# schema0_1.net
KiCad netlist of a schematic drawn in EAGLE
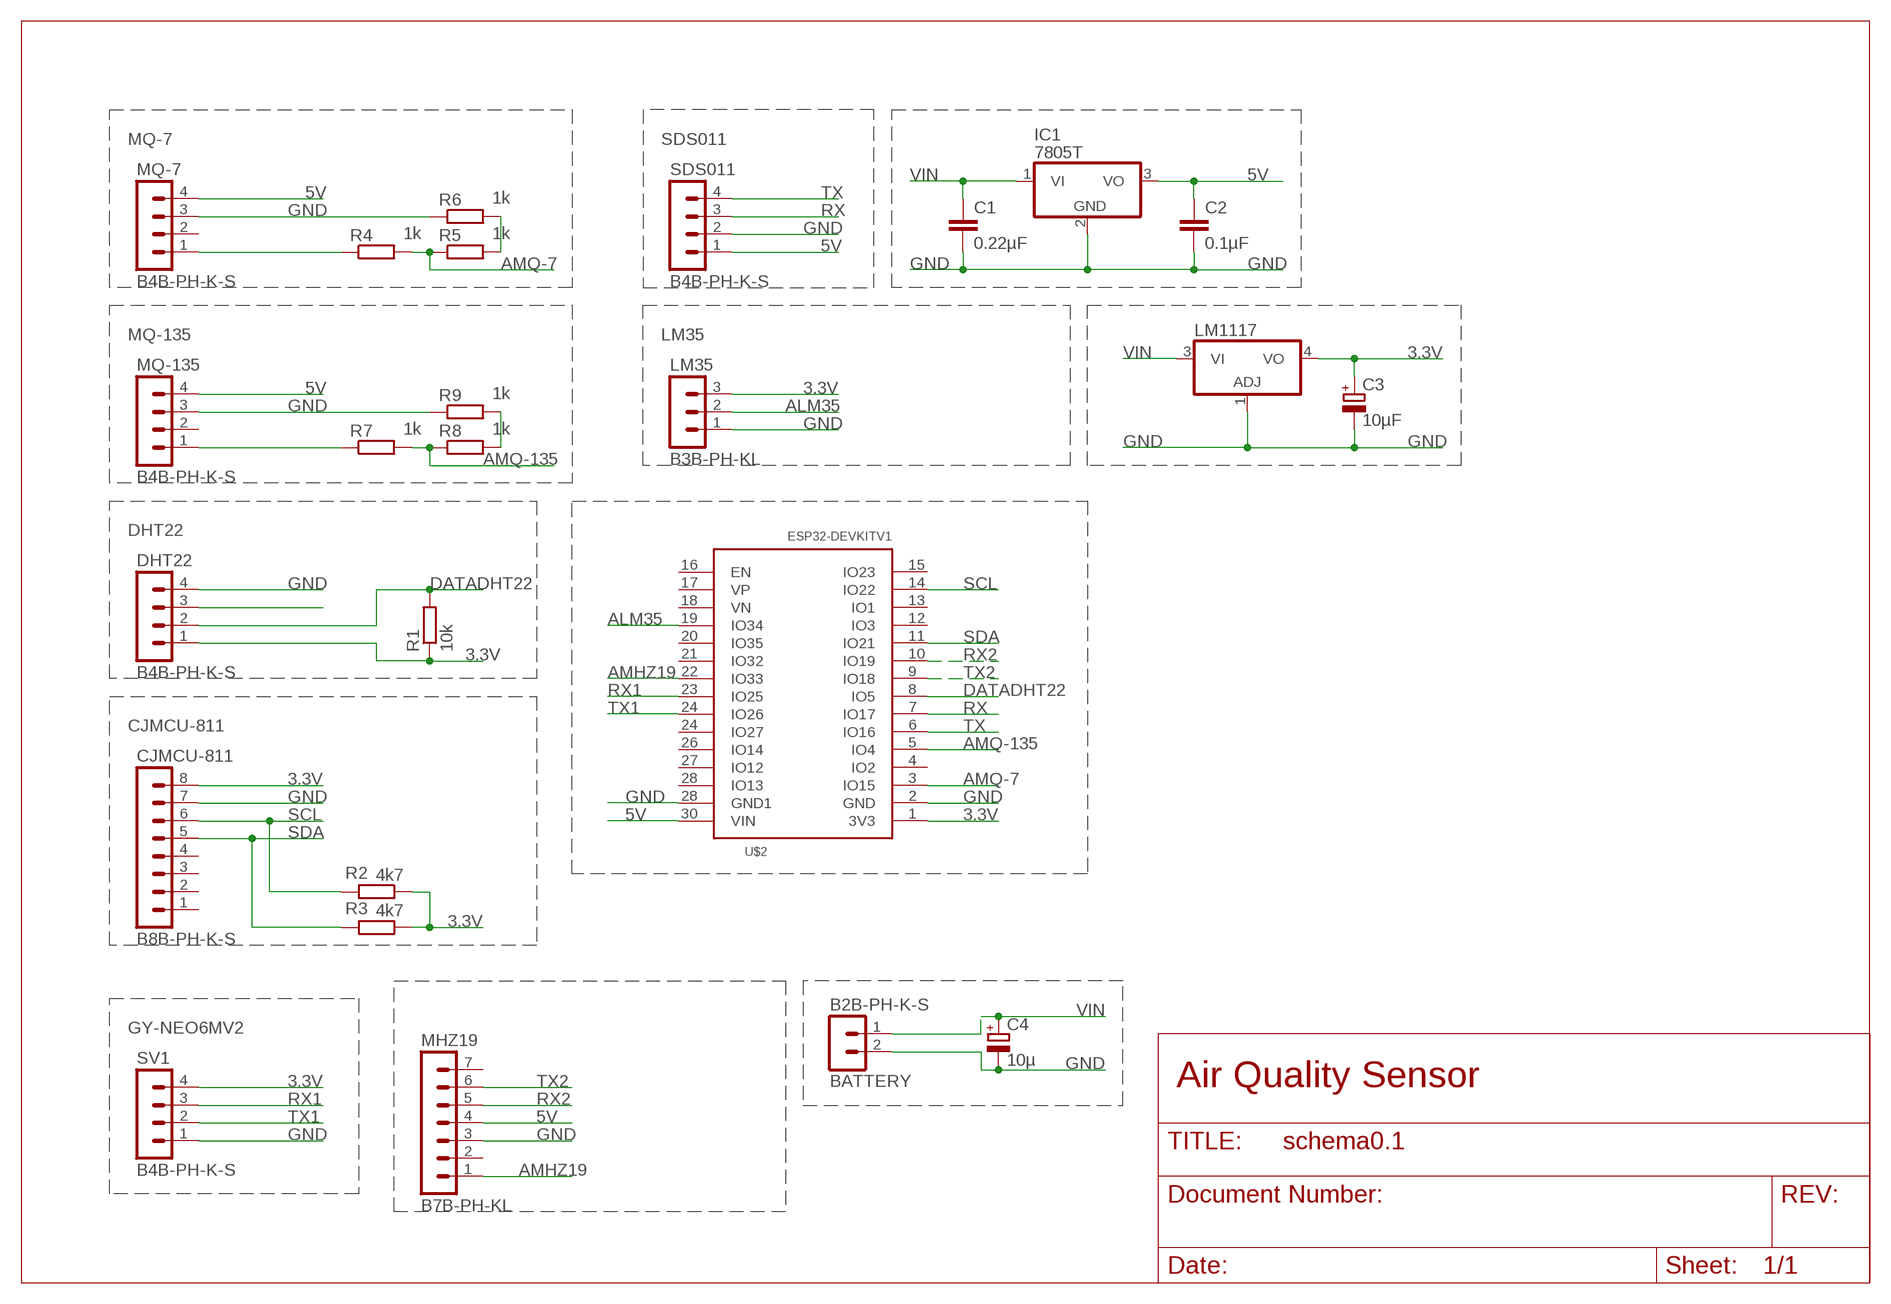
[diagram p0: schematic, sheet 1]

(export (version "E")
  (design (tool "Eeschema 10.0.6"))
  (components
    (comp (ref "BATTERY")
      (value "B2B-PH-K-S")
      (footprint "eagle-import:B2B-PH-K-S")
      (libsource (lib "eagle-import") (part "B2B-PH-K-S"))
    )
    (comp (ref "C1")
      (value "0.22µF")
      (footprint "eagle-import:C0805")
      (libsource (lib "eagle-import") (part "C-EUC0805"))
    )
    (comp (ref "C2")
      (value "0.1µF")
      (footprint "eagle-import:C0805")
      (libsource (lib "eagle-import") (part "C-EUC0805"))
    )
    (comp (ref "C3")
      (value "10µF")
      (footprint "eagle-import:E2-5")
      (libsource (lib "eagle-import") (part "CPOL-EUE2-5"))
    )
    (comp (ref "C4")
      (value "10µ")
      (footprint "eagle-import:E2-5")
      (libsource (lib "eagle-import") (part "CPOL-EUE2-5"))
    )
    (comp (ref "CJMCU-811")
      (value "B8B-PH-K-S")
      (footprint "eagle-import:B8B-PH-K-S")
      (libsource (lib "eagle-import") (part "B8B-PH-K-S"))
    )
    (comp (ref "DHT22")
      (value "B4B-PH-K-S")
      (footprint "eagle-import:B4B-PH-K-S")
      (libsource (lib "eagle-import") (part "B4B-PH-K-S"))
    )
    (comp (ref "IC1")
      (value "7805T")
      (footprint "eagle-import:TO220H")
      (libsource (lib "eagle-import") (part "78T05"))
    )
    (comp (ref "LM35")
      (value "B3B-PH-KL")
      (footprint "eagle-import:B3B-PH-K-S")
      (libsource (lib "eagle-import") (part "B3B-PH-KL"))
    )
    (comp (ref "LM1117")
      (value "317EMP")
      (footprint "eagle-import:SOT223")
      (libsource (lib "eagle-import") (part "317EMP"))
    )
    (comp (ref "MHZ19")
      (value "B7B-PH-KL")
      (footprint "eagle-import:B7B-PH-K-S")
      (libsource (lib "eagle-import") (part "B7B-PH-KL"))
    )
    (comp (ref "MQ-7")
      (value "B4B-PH-K-S")
      (footprint "eagle-import:B4B-PH-K-S")
      (libsource (lib "eagle-import") (part "B4B-PH-K-S"))
    )
    (comp (ref "MQ-135")
      (value "B4B-PH-K-S")
      (footprint "eagle-import:B4B-PH-K-S")
      (libsource (lib "eagle-import") (part "B4B-PH-K-S"))
    )
    (comp (ref "R1")
      (value "10k")
      (footprint "eagle-import:R0805")
      (libsource (lib "eagle-import") (part "R-EU_R0805"))
    )
    (comp (ref "R2")
      (value "4k7")
      (footprint "eagle-import:R0805")
      (libsource (lib "eagle-import") (part "R-EU_R0805"))
    )
    (comp (ref "R3")
      (value "4k7")
      (footprint "eagle-import:R0805")
      (libsource (lib "eagle-import") (part "R-EU_R0805"))
    )
    (comp (ref "R4")
      (value "1k")
      (footprint "eagle-import:0207_10")
      (libsource (lib "eagle-import") (part "R-EU_0207/10"))
    )
    (comp (ref "R5")
      (value "1k")
      (footprint "eagle-import:R0805")
      (libsource (lib "eagle-import") (part "R-EU_R0805"))
    )
    (comp (ref "R6")
      (value "1k")
      (footprint "eagle-import:R0805")
      (libsource (lib "eagle-import") (part "R-EU_R0805"))
    )
    (comp (ref "R7")
      (value "1k")
      (footprint "eagle-import:R0805")
      (libsource (lib "eagle-import") (part "R-EU_R0805"))
    )
    (comp (ref "R8")
      (value "1k")
      (footprint "eagle-import:R0805")
      (libsource (lib "eagle-import") (part "R-EU_R0805"))
    )
    (comp (ref "R9")
      (value "1k")
      (footprint "eagle-import:R0805")
      (libsource (lib "eagle-import") (part "R-EU_R0805"))
    )
    (comp (ref "SDS011")
      (value "B4B-PH-K-S")
      (footprint "eagle-import:B4B-PH-K-S")
      (libsource (lib "eagle-import") (part "B4B-PH-K-S"))
    )
    (comp (ref "SV1")
      (value "B4B-PH-K-S")
      (footprint "eagle-import:B4B-PH-K-S")
      (libsource (lib "eagle-import") (part "B4B-PH-K-S"))
    )
    (comp (ref "U$2")
      (value "ESP32DEVKITV1")
      (footprint "eagle-import:ESP32-DEVKITV1")
      (libsource (lib "eagle-import") (part "ESP32DEVKITV1"))
    )
  )
  (nets
    (net (code "1") (name "/3.3V") (class "Default")
      (node (ref "C3") (pin "+") (pinfunction "+_+") (pintype "passive"))
      (node (ref "CJMCU-811") (pin "8") (pinfunction "8_8") (pintype "passive"))
      (node (ref "DHT22") (pin "1") (pinfunction "1_1") (pintype "passive"))
      (node (ref "LM1117") (pin "4") (pinfunction "VO_4") (pintype "passive"))
      (node (ref "LM35") (pin "3") (pinfunction "3_3") (pintype "passive"))
      (node (ref "R1") (pin "1") (pinfunction "1_1") (pintype "passive"))
      (node (ref "R2") (pin "1") (pinfunction "1_1") (pintype "passive"))
      (node (ref "R3") (pin "1") (pinfunction "1_1") (pintype "passive"))
      (node (ref "SV1") (pin "4") (pinfunction "4_4") (pintype "passive"))
      (node (ref "U$2") (pin "1") (pinfunction "3V3_1") (pintype "bidirectional"))
    )
    (net (code "2") (name "/5V") (class "Default")
      (node (ref "C2") (pin "1") (pinfunction "1_1") (pintype "passive"))
      (node (ref "IC1") (pin "3") (pinfunction "VO_3") (pintype "passive"))
      (node (ref "MHZ19") (pin "4") (pinfunction "4_4") (pintype "passive"))
      (node (ref "MQ-135") (pin "4") (pinfunction "4_4") (pintype "passive"))
      (node (ref "MQ-7") (pin "4") (pinfunction "4_4") (pintype "passive"))
      (node (ref "SDS011") (pin "1") (pinfunction "1_1") (pintype "passive"))
      (node (ref "U$2") (pin "30") (pinfunction "VIN_30") (pintype "bidirectional"))
    )
    (net (code "3") (name "/ALM35") (class "Default")
      (node (ref "LM35") (pin "2") (pinfunction "2_2") (pintype "passive"))
      (node (ref "U$2") (pin "19") (pinfunction "IO34_19") (pintype "bidirectional"))
    )
    (net (code "4") (name "/AMHZ19") (class "Default")
      (node (ref "MHZ19") (pin "1") (pinfunction "1_1") (pintype "passive"))
      (node (ref "U$2") (pin "22") (pinfunction "IO33_22") (pintype "bidirectional"))
    )
    (net (code "5") (name "/AMQ-7") (class "Default")
      (node (ref "R4") (pin "2") (pinfunction "2_2") (pintype "passive"))
      (node (ref "R5") (pin "1") (pinfunction "1_1") (pintype "passive"))
      (node (ref "U$2") (pin "3") (pinfunction "IO15_3") (pintype "bidirectional"))
    )
    (net (code "6") (name "/AMQ-135") (class "Default")
      (node (ref "R7") (pin "2") (pinfunction "2_2") (pintype "passive"))
      (node (ref "R8") (pin "1") (pinfunction "1_1") (pintype "passive"))
      (node (ref "U$2") (pin "5") (pinfunction "IO4_5") (pintype "bidirectional"))
    )
    (net (code "7") (name "/DATADHT22") (class "Default")
      (node (ref "DHT22") (pin "2") (pinfunction "2_2") (pintype "passive"))
      (node (ref "R1") (pin "2") (pinfunction "2_2") (pintype "passive"))
      (node (ref "U$2") (pin "8") (pinfunction "IO5_8") (pintype "bidirectional"))
    )
    (net (code "8") (name "/GND") (class "Default")
      (node (ref "BATTERY") (pin "2") (pinfunction "2_2") (pintype "passive"))
      (node (ref "C1") (pin "2") (pinfunction "2_2") (pintype "passive"))
      (node (ref "C2") (pin "2") (pinfunction "2_2") (pintype "passive"))
      (node (ref "C3") (pin "-") (pinfunction "-_-") (pintype "passive"))
      (node (ref "C4") (pin "-") (pinfunction "-_-") (pintype "passive"))
      (node (ref "CJMCU-811") (pin "7") (pinfunction "7_7") (pintype "passive"))
      (node (ref "DHT22") (pin "4") (pinfunction "4_4") (pintype "passive"))
      (node (ref "IC1") (pin "2") (pinfunction "GND_2") (pintype "passive"))
      (node (ref "LM1117") (pin "1") (pinfunction "ADJ_1") (pintype "input"))
      (node (ref "LM35") (pin "1") (pinfunction "1_1") (pintype "passive"))
      (node (ref "MHZ19") (pin "3") (pinfunction "3_3") (pintype "passive"))
      (node (ref "MQ-135") (pin "3") (pinfunction "3_3") (pintype "passive"))
      (node (ref "MQ-7") (pin "3") (pinfunction "3_3") (pintype "passive"))
      (node (ref "R6") (pin "1") (pinfunction "1_1") (pintype "passive"))
      (node (ref "R9") (pin "1") (pinfunction "1_1") (pintype "passive"))
      (node (ref "SDS011") (pin "2") (pinfunction "2_2") (pintype "passive"))
      (node (ref "SV1") (pin "1") (pinfunction "1_1") (pintype "passive"))
      (node (ref "U$2") (pin "2") (pinfunction "GND_2") (pintype "bidirectional"))
      (node (ref "U$2") (pin "28") (pinfunction "GND1_28") (pintype "bidirectional"))
    )
    (net (code "9") (name "/RX") (class "Default")
      (node (ref "SDS011") (pin "3") (pinfunction "3_3") (pintype "passive"))
      (node (ref "U$2") (pin "7") (pinfunction "IO17_7") (pintype "bidirectional"))
    )
    (net (code "10") (name "/RX1") (class "Default")
      (node (ref "SV1") (pin "3") (pinfunction "3_3") (pintype "passive"))
      (node (ref "U$2") (pin "23") (pinfunction "IO25_23") (pintype "bidirectional"))
    )
    (net (code "11") (name "/RX2") (class "Default")
      (node (ref "MHZ19") (pin "5") (pinfunction "5_5") (pintype "passive"))
      (node (ref "U$2") (pin "10") (pinfunction "IO19_10") (pintype "bidirectional"))
    )
    (net (code "12") (name "/SCL") (class "Default")
      (node (ref "CJMCU-811") (pin "6") (pinfunction "6_6") (pintype "passive"))
      (node (ref "R2") (pin "2") (pinfunction "2_2") (pintype "passive"))
      (node (ref "U$2") (pin "14") (pinfunction "IO22_14") (pintype "bidirectional"))
    )
    (net (code "13") (name "/SDA") (class "Default")
      (node (ref "CJMCU-811") (pin "5") (pinfunction "5_5") (pintype "passive"))
      (node (ref "R3") (pin "2") (pinfunction "2_2") (pintype "passive"))
      (node (ref "U$2") (pin "11") (pinfunction "IO21_11") (pintype "bidirectional"))
    )
    (net (code "14") (name "/TX") (class "Default")
      (node (ref "SDS011") (pin "4") (pinfunction "4_4") (pintype "passive"))
      (node (ref "U$2") (pin "6") (pinfunction "IO16_6") (pintype "bidirectional"))
    )
    (net (code "15") (name "/TX1") (class "Default")
      (node (ref "SV1") (pin "2") (pinfunction "2_2") (pintype "passive"))
      (node (ref "U$2") (pin "24") (pinfunction "IO26_24") (pintype "bidirectional"))
    )
    (net (code "16") (name "/TX2") (class "Default")
      (node (ref "MHZ19") (pin "6") (pinfunction "6_6") (pintype "passive"))
      (node (ref "U$2") (pin "9") (pinfunction "IO18_9") (pintype "bidirectional"))
    )
    (net (code "17") (name "/VIN") (class "Default")
      (node (ref "BATTERY") (pin "1") (pinfunction "1_1") (pintype "passive"))
      (node (ref "C1") (pin "1") (pinfunction "1_1") (pintype "passive"))
      (node (ref "C4") (pin "+") (pinfunction "+_+") (pintype "passive"))
      (node (ref "IC1") (pin "1") (pinfunction "VI_1") (pintype "input"))
      (node (ref "LM1117") (pin "3") (pinfunction "VI_3") (pintype "input"))
    )
    (net (code "18") (name "Net-(MQ-7-Pad1)") (class "Default")
      (node (ref "MQ-7") (pin "1") (pinfunction "1_1") (pintype "passive"))
      (node (ref "R4") (pin "1") (pinfunction "1_1") (pintype "passive"))
    )
    (net (code "19") (name "Net-(MQ-135-Pad1)") (class "Default")
      (node (ref "MQ-135") (pin "1") (pinfunction "1_1") (pintype "passive"))
      (node (ref "R7") (pin "1") (pinfunction "1_1") (pintype "passive"))
    )
    (net (code "20") (name "Net-(R5-Pad2)") (class "Default")
      (node (ref "R5") (pin "2") (pinfunction "2_2") (pintype "passive"))
      (node (ref "R6") (pin "2") (pinfunction "2_2") (pintype "passive"))
    )
    (net (code "21") (name "Net-(R8-Pad2)") (class "Default")
      (node (ref "R8") (pin "2") (pinfunction "2_2") (pintype "passive"))
      (node (ref "R9") (pin "2") (pinfunction "2_2") (pintype "passive"))
    )
    (net (code "22") (name "unconnected-(CJMCU-811-Pad1)") (class "Default")
      (node (ref "CJMCU-811") (pin "1") (pinfunction "1_1") (pintype "passive"))
    )
    (net (code "23") (name "unconnected-(CJMCU-811-Pad2)") (class "Default")
      (node (ref "CJMCU-811") (pin "2") (pinfunction "2_2") (pintype "passive"))
    )
    (net (code "24") (name "unconnected-(CJMCU-811-Pad3)") (class "Default")
      (node (ref "CJMCU-811") (pin "3") (pinfunction "3_3") (pintype "passive"))
    )
    (net (code "25") (name "unconnected-(CJMCU-811-Pad4)") (class "Default")
      (node (ref "CJMCU-811") (pin "4") (pinfunction "4_4") (pintype "passive"))
    )
    (net (code "26") (name "unconnected-(DHT22-Pad3)") (class "Default")
      (node (ref "DHT22") (pin "3") (pinfunction "3_3") (pintype "passive"))
    )
    (net (code "27") (name "unconnected-(MHZ19-Pad2)") (class "Default")
      (node (ref "MHZ19") (pin "2") (pinfunction "2_2") (pintype "passive"))
    )
    (net (code "28") (name "unconnected-(MHZ19-Pad7)") (class "Default")
      (node (ref "MHZ19") (pin "7") (pinfunction "7_7") (pintype "passive"))
    )
    (net (code "29") (name "unconnected-(MQ-7-Pad2)") (class "Default")
      (node (ref "MQ-7") (pin "2") (pinfunction "2_2") (pintype "passive"))
    )
    (net (code "30") (name "unconnected-(MQ-135-Pad2)") (class "Default")
      (node (ref "MQ-135") (pin "2") (pinfunction "2_2") (pintype "passive"))
    )
    (net (code "31") (name "unconnected-(U$2-EN-Pad16)") (class "Default")
      (node (ref "U$2") (pin "16") (pinfunction "EN_16") (pintype "bidirectional"))
    )
    (net (code "32") (name "unconnected-(U$2-IO1-Pad13)") (class "Default")
      (node (ref "U$2") (pin "13") (pinfunction "IO1_13") (pintype "bidirectional"))
    )
    (net (code "33") (name "unconnected-(U$2-IO2-Pad4)") (class "Default")
      (node (ref "U$2") (pin "4") (pinfunction "IO2_4") (pintype "bidirectional"))
    )
    (net (code "34") (name "unconnected-(U$2-IO3-Pad12)") (class "Default")
      (node (ref "U$2") (pin "12") (pinfunction "IO3_12") (pintype "bidirectional"))
    )
    (net (code "35") (name "unconnected-(U$2-IO12-Pad27)") (class "Default")
      (node (ref "U$2") (pin "27") (pinfunction "IO12_27") (pintype "bidirectional"))
    )
    (net (code "36") (name "unconnected-(U$2-IO13-Pad28)") (class "Default")
      (node (ref "U$2") (pin "28") (pinfunction "IO13_28") (pintype "bidirectional"))
    )
    (net (code "37") (name "unconnected-(U$2-IO14-Pad26)") (class "Default")
      (node (ref "U$2") (pin "26") (pinfunction "IO14_26") (pintype "bidirectional"))
    )
    (net (code "38") (name "unconnected-(U$2-IO23-Pad15)") (class "Default")
      (node (ref "U$2") (pin "15") (pinfunction "IO23_15") (pintype "bidirectional"))
    )
    (net (code "39") (name "unconnected-(U$2-IO27-Pad24)") (class "Default")
      (node (ref "U$2") (pin "24") (pinfunction "IO27_24") (pintype "bidirectional"))
    )
    (net (code "40") (name "unconnected-(U$2-IO32-Pad21)") (class "Default")
      (node (ref "U$2") (pin "21") (pinfunction "IO32_21") (pintype "bidirectional"))
    )
    (net (code "41") (name "unconnected-(U$2-IO35-Pad20)") (class "Default")
      (node (ref "U$2") (pin "20") (pinfunction "IO35_20") (pintype "bidirectional"))
    )
    (net (code "42") (name "unconnected-(U$2-VN-Pad18)") (class "Default")
      (node (ref "U$2") (pin "18") (pinfunction "VN_18") (pintype "bidirectional"))
    )
    (net (code "43") (name "unconnected-(U$2-VP-Pad17)") (class "Default")
      (node (ref "U$2") (pin "17") (pinfunction "VP_17") (pintype "bidirectional"))
    )
  )
)
